# NinoTNC_BLE.net
KiCad netlist of a schematic drawn in EAGLE
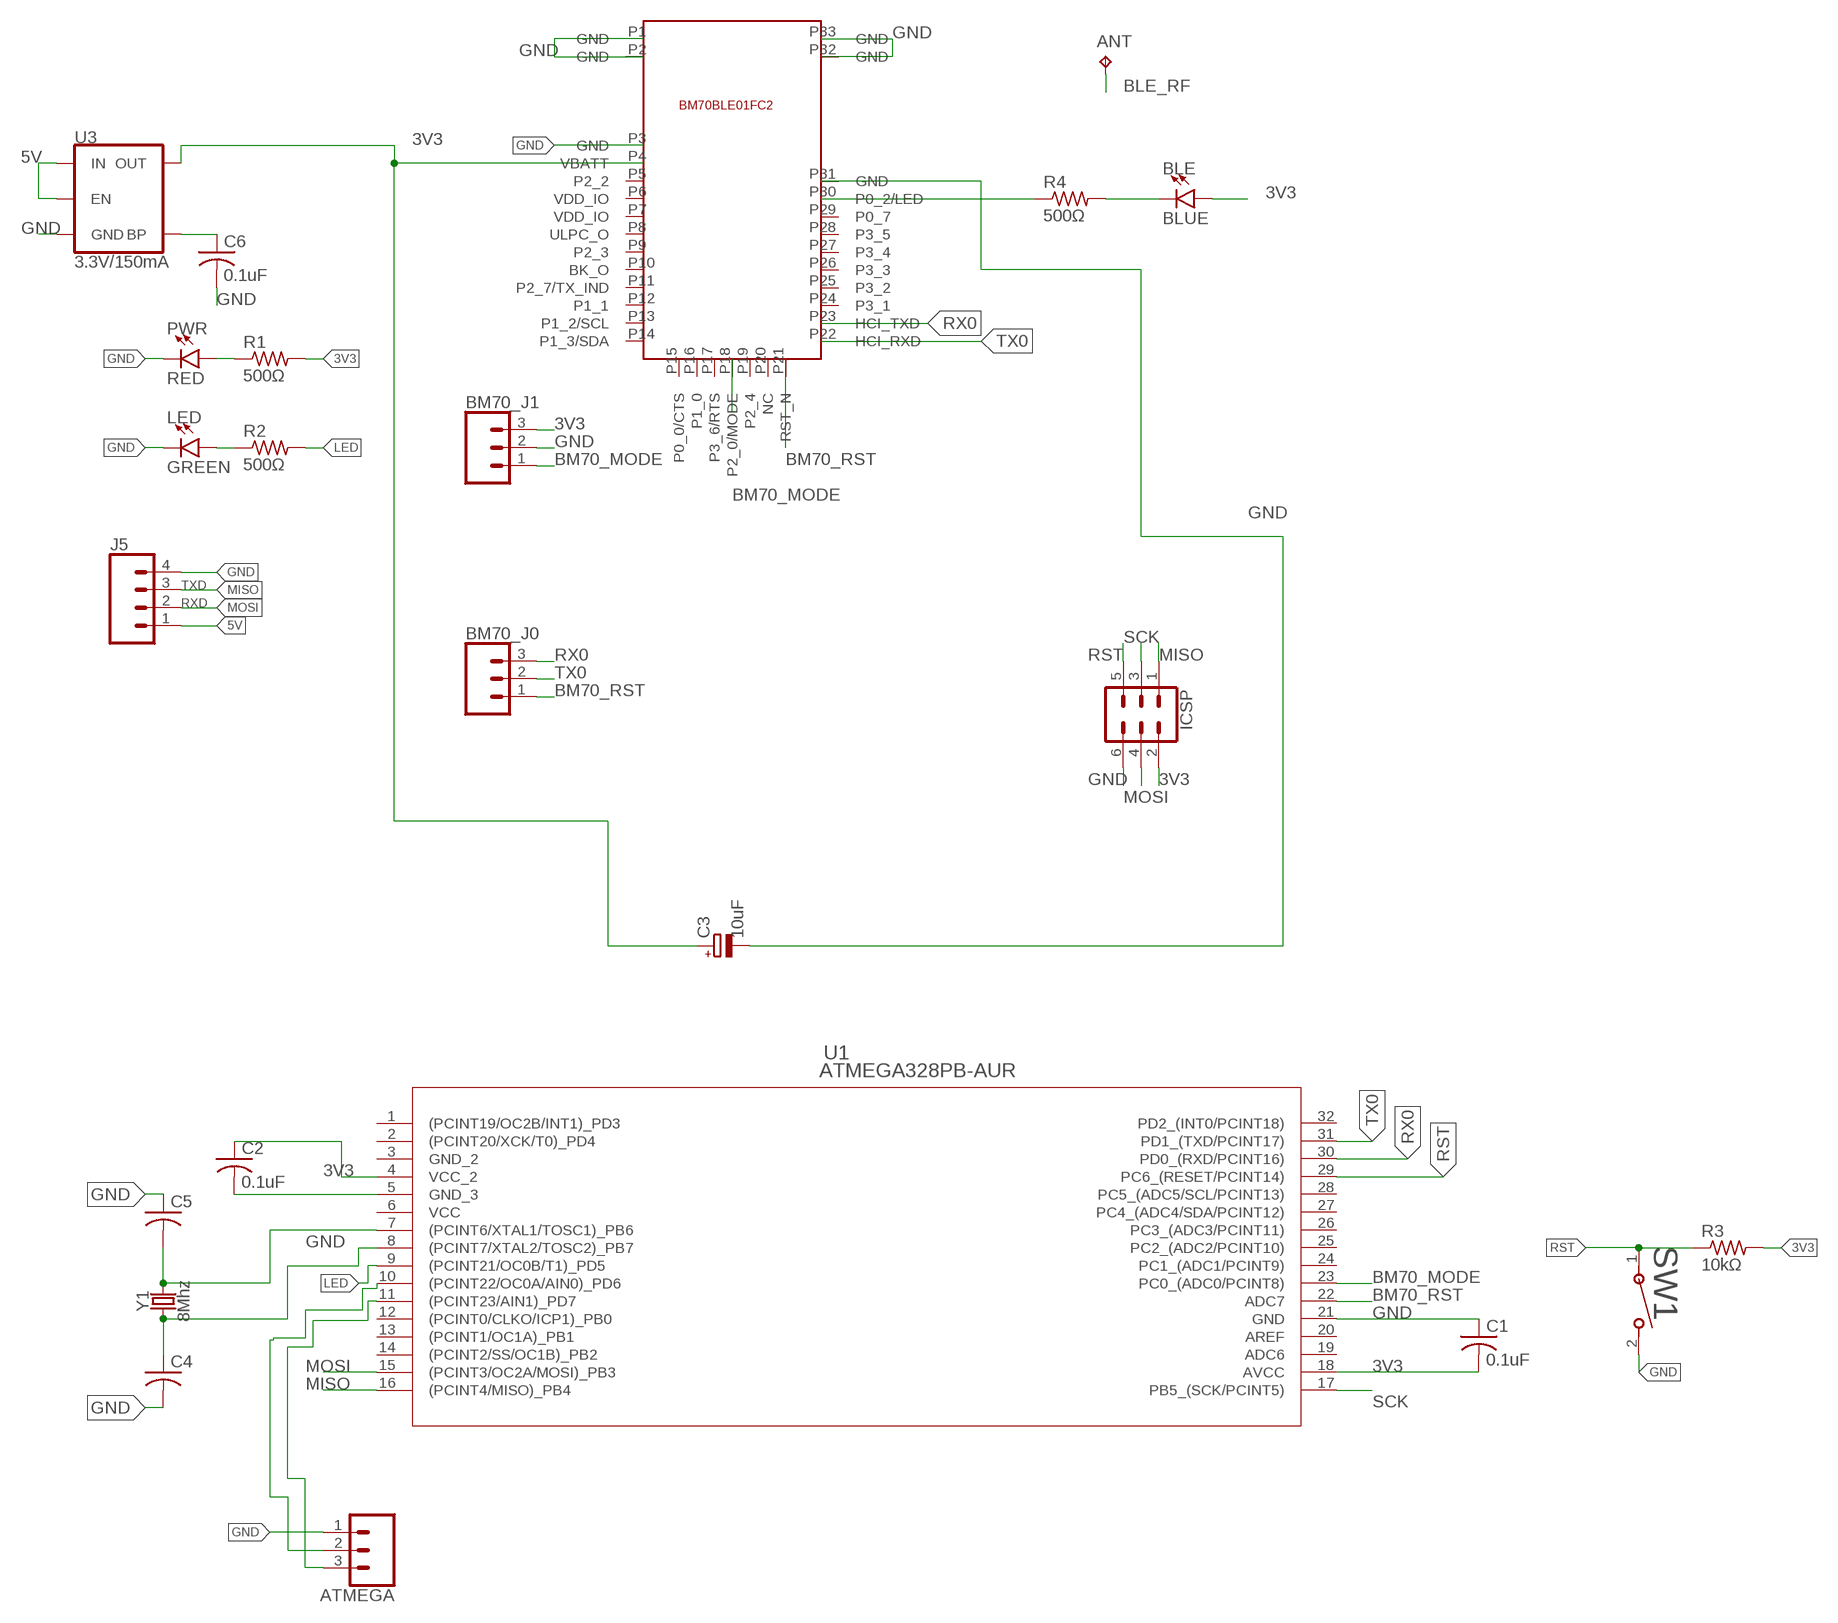
[diagram p0: schematic, sheet 1]

(export (version "E")
  (design (tool "Eeschema 10.0.6"))
  (components
    (comp (ref "ANT")
      (value "TPTP08SQ")
      (footprint "eagle-import:TP08SQ")
      (libsource (lib "eagle-import") (part "TPTP08SQ"))
    )
    (comp (ref "ATMEGA")
      (value "CONN_03")
      (footprint "eagle-import:1X03")
      (libsource (lib "eagle-import") (part "CONN_03"))
    )
    (comp (ref "BLE")
      (value "BLUE")
      (footprint "eagle-import:LED-0603")
      (libsource (lib "eagle-import") (part "LED-RED0603"))
    )
    (comp (ref "BM70_J0")
      (value "CONN_03")
      (footprint "eagle-import:1X03")
      (libsource (lib "eagle-import") (part "CONN_03"))
    )
    (comp (ref "BM70_J1")
      (value "CONN_03")
      (footprint "eagle-import:1X03")
      (libsource (lib "eagle-import") (part "CONN_03"))
    )
    (comp (ref "C1")
      (value "0.1uF")
      (footprint "eagle-import:C0805")
      (libsource (lib "eagle-import") (part "C-USC0805"))
    )
    (comp (ref "C2")
      (value "0.1uF")
      (footprint "eagle-import:C0805")
      (libsource (lib "eagle-import") (part "C-USC0805"))
    )
    (comp (ref "C3")
      (value "10uF")
      (footprint "eagle-import:SMC_A")
      (libsource (lib "eagle-import") (part "CAPACITOR_POL-SMC_A"))
    )
    (comp (ref "C4")
      (value "22pF")
      (footprint "eagle-import:C0805")
      (libsource (lib "eagle-import") (part "adafruit_420_C-USC0805"))
    )
    (comp (ref "C5")
      (value "22pF")
      (footprint "eagle-import:C0805")
      (libsource (lib "eagle-import") (part "adafruit_420_C-USC0805"))
    )
    (comp (ref "C6")
      (value "0.1uF")
      (footprint "eagle-import:C0805")
      (libsource (lib "eagle-import") (part "C-USC0805"))
    )
    (comp (ref "ICSP")
      (value "CONN_03X22X3_SILK_MALE_PTH")
      (footprint "eagle-import:2X3")
      (libsource (lib "eagle-import") (part "CONN_03X22X3_SILK_MALE_PTH"))
    )
    (comp (ref "J5")
      (value "CONN_04")
      (footprint "eagle-import:1X04")
      (libsource (lib "eagle-import") (part "CONN_04"))
    )
    (comp (ref "LED")
      (value "GREEN")
      (footprint "eagle-import:LED-0603")
      (libsource (lib "eagle-import") (part "LED-RED0603"))
    )
    (comp (ref "PWR")
      (value "RED")
      (footprint "eagle-import:LED-0603")
      (libsource (lib "eagle-import") (part "LED-RED0603"))
    )
    (comp (ref "R1")
      (value "500Ω")
      (footprint "eagle-import:M0805")
      (libsource (lib "eagle-import") (part "R-US_M0805"))
    )
    (comp (ref "R2")
      (value "500Ω")
      (footprint "eagle-import:M0805")
      (libsource (lib "eagle-import") (part "R-US_M0805"))
    )
    (comp (ref "R3")
      (value "10kΩ")
      (footprint "eagle-import:R0805")
      (libsource (lib "eagle-import") (part "R-US_R0805"))
    )
    (comp (ref "R4")
      (value "500Ω")
      (footprint "eagle-import:M0805")
      (libsource (lib "eagle-import") (part "R-US_M0805"))
    )
    (comp (ref "SW1")
      (value "EVQ-PE105K")
      (footprint "eagle-import:EVQPE_5_PAN")
      (fields (field (name "COPYRIGHT") "Copyright (C) 2018 Accelerated Designs. All rights reserved"))
      (libsource (lib "eagle-import") (part "EVQ-PE105K"))
    )
    (comp (ref "U$1")
      (value "BM70BLE01FC2")
      (footprint "eagle-import:BM70BLE01FC2")
      (libsource (lib "eagle-import") (part "BM70BLE01FC2"))
    )
    (comp (ref "U1")
      (value "ATMEGA328PB-AUR")
      (footprint "eagle-import:32A_MCH")
      (fields (field (name "COPYRIGHT") "Copyright (C) 2018 Accelerated Designs. All rights reserved"))
      (libsource (lib "eagle-import") (part "ATMEGA328PB-AUR"))
    )
    (comp (ref "U3")
      (value "3.3V/150mA")
      (footprint "eagle-import:SOT23-5")
      (libsource (lib "eagle-import") (part "V_REG_MIC52053.3V"))
    )
    (comp (ref "Y1")
      (value "8Mhz")
      (footprint "eagle-import:HC49U")
      (libsource (lib "eagle-import") (part "CRYSTALPTH-HC49UV"))
    )
  )
  (nets
    (net (code "1") (name "/BLE_RF") (class "Default")
      (node (ref "ANT") (pin "TP") (pinfunction "TP_TP") (pintype "input"))
    )
    (net (code "2") (name "/BM70_MODE") (class "Default")
      (node (ref "BM70_J1") (pin "1") (pinfunction "1_1") (pintype "passive"))
      (node (ref "U$1") (pin "P18") (pinfunction "P2_0/MODE_P18") (pintype "bidirectional"))
      (node (ref "U1") (pin "23") (pinfunction "PC0_(ADC0/PCINT8)_23") (pintype "bidirectional"))
    )
    (net (code "3") (name "/BM70_RST") (class "Default")
      (node (ref "BM70_J0") (pin "1") (pinfunction "1_1") (pintype "passive"))
      (node (ref "U$1") (pin "P21") (pinfunction "RST_N_P21") (pintype "bidirectional"))
      (node (ref "U1") (pin "22") (pinfunction "ADC7_22") (pintype "input"))
    )
    (net (code "4") (name "/GND_2") (class "Default")
      (node (ref "U1") (pin "3") (pinfunction "GND_2_3") (pintype "power_in"))
    )
    (net (code "5") (name "/SCK") (class "Default")
      (node (ref "ICSP") (pin "3") (pinfunction "3_3") (pintype "bidirectional"))
      (node (ref "U1") (pin "17") (pinfunction "PB5_(SCK/PCINT5)_17") (pintype "bidirectional"))
    )
    (net (code "6") (name "/VCC") (class "Default")
      (node (ref "U1") (pin "6") (pinfunction "VCC_6") (pintype "power_in"))
    )
    (net (code "7") (name "3V3") (class "Default")
      (node (ref "BLE") (pin "A") (pinfunction "A_A") (pintype "passive"))
      (node (ref "BM70_J1") (pin "3") (pinfunction "3_3") (pintype "passive"))
      (node (ref "C1") (pin "2") (pinfunction "2_2") (pintype "passive"))
      (node (ref "C2") (pin "1") (pinfunction "1_1") (pintype "passive"))
      (node (ref "C3") (pin "+") (pinfunction "+_+") (pintype "passive"))
      (node (ref "ICSP") (pin "2") (pinfunction "2_2") (pintype "bidirectional"))
      (node (ref "R1") (pin "2") (pinfunction "2_2") (pintype "passive"))
      (node (ref "R3") (pin "2") (pinfunction "2_2") (pintype "passive"))
      (node (ref "U$1") (pin "P4") (pinfunction "VBATT_P4") (pintype "bidirectional"))
      (node (ref "U1") (pin "18") (pinfunction "AVCC_18") (pintype "power_in"))
      (node (ref "U1") (pin "4") (pinfunction "VCC_2_4") (pintype "power_in"))
      (node (ref "U3") (pin "5") (pinfunction "OUT_5") (pintype "passive"))
    )
    (net (code "8") (name "5V") (class "Default")
      (node (ref "J5") (pin "1") (pinfunction "1_1") (pintype "passive"))
      (node (ref "U3") (pin "1") (pinfunction "IN_1") (pintype "input"))
      (node (ref "U3") (pin "3") (pinfunction "EN_3") (pintype "input"))
    )
    (net (code "9") (name "GND") (class "Default")
      (node (ref "ATMEGA") (pin "1") (pinfunction "1_1") (pintype "passive"))
      (node (ref "BM70_J1") (pin "2") (pinfunction "2_2") (pintype "passive"))
      (node (ref "C1") (pin "1") (pinfunction "1_1") (pintype "passive"))
      (node (ref "C2") (pin "2") (pinfunction "2_2") (pintype "passive"))
      (node (ref "C3") (pin "-") (pinfunction "-_-") (pintype "passive"))
      (node (ref "C4") (pin "2") (pinfunction "2_2") (pintype "passive"))
      (node (ref "C5") (pin "1") (pinfunction "1_1") (pintype "passive"))
      (node (ref "C6") (pin "2") (pinfunction "2_2") (pintype "passive"))
      (node (ref "ICSP") (pin "6") (pinfunction "6_6") (pintype "bidirectional"))
      (node (ref "J5") (pin "4") (pinfunction "4_4") (pintype "passive"))
      (node (ref "LED") (pin "C") (pinfunction "C_C") (pintype "passive"))
      (node (ref "PWR") (pin "C") (pinfunction "C_C") (pintype "passive"))
      (node (ref "SW1") (pin "2") (pinfunction "2_2") (pintype "passive"))
      (node (ref "U$1") (pin "P1") (pinfunction "GND_P1") (pintype "bidirectional"))
      (node (ref "U$1") (pin "P2") (pinfunction "GND_P2") (pintype "bidirectional"))
      (node (ref "U$1") (pin "P3") (pinfunction "GND_P3") (pintype "bidirectional"))
      (node (ref "U$1") (pin "P31") (pinfunction "GND_P31") (pintype "bidirectional"))
      (node (ref "U$1") (pin "P32") (pinfunction "GND_P32") (pintype "bidirectional"))
      (node (ref "U$1") (pin "P33") (pinfunction "GND_P33") (pintype "bidirectional"))
      (node (ref "U1") (pin "21") (pinfunction "GND_21") (pintype "power_in"))
      (node (ref "U1") (pin "5") (pinfunction "GND_3_5") (pintype "power_in"))
      (node (ref "U3") (pin "2") (pinfunction "GND_2") (pintype "input"))
    )
    (net (code "10") (name "LED") (class "Default")
      (node (ref "R2") (pin "2") (pinfunction "2_2") (pintype "passive"))
      (node (ref "U1") (pin "9") (pinfunction "(PCINT21/OC0B/T1)_PD5_9") (pintype "bidirectional"))
    )
    (net (code "11") (name "MISO") (class "Default")
      (node (ref "ICSP") (pin "1") (pinfunction "1_1") (pintype "bidirectional"))
      (node (ref "J5") (pin "3") (pinfunction "3_3") (pintype "passive"))
      (node (ref "U1") (pin "16") (pinfunction "(PCINT4/MISO)_PB4_16") (pintype "bidirectional"))
    )
    (net (code "12") (name "MOSI") (class "Default")
      (node (ref "ICSP") (pin "4") (pinfunction "4_4") (pintype "bidirectional"))
      (node (ref "J5") (pin "2") (pinfunction "2_2") (pintype "passive"))
      (node (ref "U1") (pin "15") (pinfunction "(PCINT3/OC2A/MOSI)_PB3_15") (pintype "bidirectional"))
    )
    (net (code "13") (name "Net-(BLE-PadC)") (class "Default")
      (node (ref "BLE") (pin "C") (pinfunction "C_C") (pintype "passive"))
      (node (ref "R4") (pin "2") (pinfunction "2_2") (pintype "passive"))
    )
    (net (code "14") (name "Net-(LED-PadA)") (class "Default")
      (node (ref "LED") (pin "A") (pinfunction "A_A") (pintype "passive"))
      (node (ref "R2") (pin "1") (pinfunction "1_1") (pintype "passive"))
    )
    (net (code "15") (name "Net-(PWR-PadA)") (class "Default")
      (node (ref "PWR") (pin "A") (pinfunction "A_A") (pintype "passive"))
      (node (ref "R1") (pin "1") (pinfunction "1_1") (pintype "passive"))
    )
    (net (code "16") (name "Net-(U$1-P0_2{slash}LED)") (class "Default")
      (node (ref "R4") (pin "1") (pinfunction "1_1") (pintype "passive"))
      (node (ref "U$1") (pin "P30") (pinfunction "P0_2/LED_P30") (pintype "bidirectional"))
    )
    (net (code "17") (name "Net-(U1-(PCINT6{slash}XTAL1{slash}TOSC1)_PB6)") (class "Default")
      (node (ref "C5") (pin "2") (pinfunction "2_2") (pintype "passive"))
      (node (ref "U1") (pin "7") (pinfunction "(PCINT6/XTAL1/TOSC1)_PB6_7") (pintype "bidirectional"))
      (node (ref "Y1") (pin "2") (pinfunction "2_2") (pintype "passive"))
    )
    (net (code "18") (name "Net-(U1-(PCINT7{slash}XTAL2{slash}TOSC2)_PB7)") (class "Default")
      (node (ref "C4") (pin "1") (pinfunction "1_1") (pintype "passive"))
      (node (ref "U1") (pin "8") (pinfunction "(PCINT7/XTAL2/TOSC2)_PB7_8") (pintype "bidirectional"))
      (node (ref "Y1") (pin "1") (pinfunction "1_1") (pintype "passive"))
    )
    (net (code "19") (name "Net-(U1-(PCINT22{slash}OC0A{slash}AIN0)_PD6)") (class "Default")
      (node (ref "ATMEGA") (pin "2") (pinfunction "2_2") (pintype "passive"))
      (node (ref "U1") (pin "10") (pinfunction "(PCINT22/OC0A/AIN0)_PD6_10") (pintype "bidirectional"))
    )
    (net (code "20") (name "Net-(U1-(PCINT23{slash}AIN1)_PD7)") (class "Default")
      (node (ref "ATMEGA") (pin "3") (pinfunction "3_3") (pintype "passive"))
      (node (ref "U1") (pin "11") (pinfunction "(PCINT23/AIN1)_PD7_11") (pintype "bidirectional"))
    )
    (net (code "21") (name "Net-(U3-BP)") (class "Default")
      (node (ref "C6") (pin "1") (pinfunction "1_1") (pintype "passive"))
      (node (ref "U3") (pin "4") (pinfunction "BP_4") (pintype "input"))
    )
    (net (code "22") (name "RST") (class "Default")
      (node (ref "ICSP") (pin "5") (pinfunction "5_5") (pintype "bidirectional"))
      (node (ref "R3") (pin "1") (pinfunction "1_1") (pintype "passive"))
      (node (ref "SW1") (pin "1") (pinfunction "1_1") (pintype "passive"))
      (node (ref "U1") (pin "29") (pinfunction "PC6_(RESET/PCINT14)_29") (pintype "bidirectional"))
    )
    (net (code "23") (name "RX0") (class "Default")
      (node (ref "BM70_J0") (pin "3") (pinfunction "3_3") (pintype "passive"))
      (node (ref "U$1") (pin "P23") (pinfunction "HCI_TXD_P23") (pintype "bidirectional"))
      (node (ref "U1") (pin "30") (pinfunction "PD0_(RXD/PCINT16)_30") (pintype "bidirectional"))
    )
    (net (code "24") (name "TX0") (class "Default")
      (node (ref "BM70_J0") (pin "2") (pinfunction "2_2") (pintype "passive"))
      (node (ref "U$1") (pin "P22") (pinfunction "HCI_RXD_P22") (pintype "bidirectional"))
      (node (ref "U1") (pin "31") (pinfunction "PD1_(TXD/PCINT17)_31") (pintype "bidirectional"))
    )
    (net (code "25") (name "unconnected-(U$1-BK_O-PadP10)") (class "Default")
      (node (ref "U$1") (pin "P10") (pinfunction "BK_O_P10") (pintype "bidirectional"))
    )
    (net (code "26") (name "unconnected-(U$1-NC-PadP20)") (class "Default")
      (node (ref "U$1") (pin "P20") (pinfunction "NC_P20") (pintype "bidirectional"))
    )
    (net (code "27") (name "unconnected-(U$1-P0_0{slash}CTS-PadP15)") (class "Default")
      (node (ref "U$1") (pin "P15") (pinfunction "P0_0/CTS_P15") (pintype "bidirectional"))
    )
    (net (code "28") (name "unconnected-(U$1-P0_7-PadP29)") (class "Default")
      (node (ref "U$1") (pin "P29") (pinfunction "P0_7_P29") (pintype "bidirectional"))
    )
    (net (code "29") (name "unconnected-(U$1-P1_0-PadP16)") (class "Default")
      (node (ref "U$1") (pin "P16") (pinfunction "P1_0_P16") (pintype "bidirectional"))
    )
    (net (code "30") (name "unconnected-(U$1-P1_1-PadP12)") (class "Default")
      (node (ref "U$1") (pin "P12") (pinfunction "P1_1_P12") (pintype "bidirectional"))
    )
    (net (code "31") (name "unconnected-(U$1-P1_2{slash}SCL-PadP13)") (class "Default")
      (node (ref "U$1") (pin "P13") (pinfunction "P1_2/SCL_P13") (pintype "bidirectional"))
    )
    (net (code "32") (name "unconnected-(U$1-P1_3{slash}SDA-PadP14)") (class "Default")
      (node (ref "U$1") (pin "P14") (pinfunction "P1_3/SDA_P14") (pintype "bidirectional"))
    )
    (net (code "33") (name "unconnected-(U$1-P2_2-PadP5)") (class "Default")
      (node (ref "U$1") (pin "P5") (pinfunction "P2_2_P5") (pintype "bidirectional"))
    )
    (net (code "34") (name "unconnected-(U$1-P2_3-PadP9)") (class "Default")
      (node (ref "U$1") (pin "P9") (pinfunction "P2_3_P9") (pintype "bidirectional"))
    )
    (net (code "35") (name "unconnected-(U$1-P2_4-PadP19)") (class "Default")
      (node (ref "U$1") (pin "P19") (pinfunction "P2_4_P19") (pintype "bidirectional"))
    )
    (net (code "36") (name "unconnected-(U$1-P2_7{slash}TX_IND-PadP11)") (class "Default")
      (node (ref "U$1") (pin "P11") (pinfunction "P2_7/TX_IND_P11") (pintype "bidirectional"))
    )
    (net (code "37") (name "unconnected-(U$1-P3_1-PadP24)") (class "Default")
      (node (ref "U$1") (pin "P24") (pinfunction "P3_1_P24") (pintype "bidirectional"))
    )
    (net (code "38") (name "unconnected-(U$1-P3_2-PadP25)") (class "Default")
      (node (ref "U$1") (pin "P25") (pinfunction "P3_2_P25") (pintype "bidirectional"))
    )
    (net (code "39") (name "unconnected-(U$1-P3_3-PadP26)") (class "Default")
      (node (ref "U$1") (pin "P26") (pinfunction "P3_3_P26") (pintype "bidirectional"))
    )
    (net (code "40") (name "unconnected-(U$1-P3_4-PadP27)") (class "Default")
      (node (ref "U$1") (pin "P27") (pinfunction "P3_4_P27") (pintype "bidirectional"))
    )
    (net (code "41") (name "unconnected-(U$1-P3_5-PadP28)") (class "Default")
      (node (ref "U$1") (pin "P28") (pinfunction "P3_5_P28") (pintype "bidirectional"))
    )
    (net (code "42") (name "unconnected-(U$1-P3_6{slash}RTS-PadP17)") (class "Default")
      (node (ref "U$1") (pin "P17") (pinfunction "P3_6/RTS_P17") (pintype "bidirectional"))
    )
    (net (code "43") (name "unconnected-(U$1-ULPC_O-PadP8)") (class "Default")
      (node (ref "U$1") (pin "P8") (pinfunction "ULPC_O_P8") (pintype "bidirectional"))
    )
    (net (code "44") (name "unconnected-(U$1-VDD_IO-PadP6)") (class "Default")
      (node (ref "U$1") (pin "P6") (pinfunction "VDD_IO_P6") (pintype "bidirectional"))
    )
    (net (code "45") (name "unconnected-(U$1-VDD_IO-PadP7)") (class "Default")
      (node (ref "U$1") (pin "P7") (pinfunction "VDD_IO_P7") (pintype "bidirectional"))
    )
    (net (code "46") (name "unconnected-(U1-(PCINT0{slash}CLKO{slash}ICP1)_PB0-Pad12)") (class "Default")
      (node (ref "U1") (pin "12") (pinfunction "(PCINT0/CLKO/ICP1)_PB0_12") (pintype "bidirectional"))
    )
    (net (code "47") (name "unconnected-(U1-(PCINT1{slash}OC1A)_PB1-Pad13)") (class "Default")
      (node (ref "U1") (pin "13") (pinfunction "(PCINT1/OC1A)_PB1_13") (pintype "bidirectional"))
    )
    (net (code "48") (name "unconnected-(U1-(PCINT2{slash}SS{slash}OC1B)_PB2-Pad14)") (class "Default")
      (node (ref "U1") (pin "14") (pinfunction "(PCINT2/SS/OC1B)_PB2_14") (pintype "bidirectional"))
    )
    (net (code "49") (name "unconnected-(U1-(PCINT19{slash}OC2B{slash}INT1)_PD3-Pad1)") (class "Default")
      (node (ref "U1") (pin "1") (pinfunction "(PCINT19/OC2B/INT1)_PD3_1") (pintype "bidirectional"))
    )
    (net (code "50") (name "unconnected-(U1-(PCINT20{slash}XCK{slash}T0)_PD4-Pad2)") (class "Default")
      (node (ref "U1") (pin "2") (pinfunction "(PCINT20/XCK/T0)_PD4_2") (pintype "bidirectional"))
    )
    (net (code "51") (name "unconnected-(U1-ADC6-Pad19)") (class "Default")
      (node (ref "U1") (pin "19") (pinfunction "ADC6_19") (pintype "input"))
    )
    (net (code "52") (name "unconnected-(U1-AREF-Pad20)") (class "Default")
      (node (ref "U1") (pin "20") (pinfunction "AREF_20") (pintype "passive"))
    )
    (net (code "53") (name "unconnected-(U1-PC1_(ADC1{slash}PCINT9)-Pad24)") (class "Default")
      (node (ref "U1") (pin "24") (pinfunction "PC1_(ADC1/PCINT9)_24") (pintype "bidirectional"))
    )
    (net (code "54") (name "unconnected-(U1-PC2_(ADC2{slash}PCINT10)-Pad25)") (class "Default")
      (node (ref "U1") (pin "25") (pinfunction "PC2_(ADC2/PCINT10)_25") (pintype "bidirectional"))
    )
    (net (code "55") (name "unconnected-(U1-PC3_(ADC3{slash}PCINT11)-Pad26)") (class "Default")
      (node (ref "U1") (pin "26") (pinfunction "PC3_(ADC3/PCINT11)_26") (pintype "bidirectional"))
    )
    (net (code "56") (name "unconnected-(U1-PC4_(ADC4{slash}SDA{slash}PCINT12)-Pad27)") (class "Default")
      (node (ref "U1") (pin "27") (pinfunction "PC4_(ADC4/SDA/PCINT12)_27") (pintype "bidirectional"))
    )
    (net (code "57") (name "unconnected-(U1-PC5_(ADC5{slash}SCL{slash}PCINT13)-Pad28)") (class "Default")
      (node (ref "U1") (pin "28") (pinfunction "PC5_(ADC5/SCL/PCINT13)_28") (pintype "bidirectional"))
    )
    (net (code "58") (name "unconnected-(U1-PD2_(INT0{slash}PCINT18)-Pad32)") (class "Default")
      (node (ref "U1") (pin "32") (pinfunction "PD2_(INT0/PCINT18)_32") (pintype "bidirectional"))
    )
  )
)
